# VS_Module.net
KiCad netlist of a schematic drawn in EasyEDA Pro
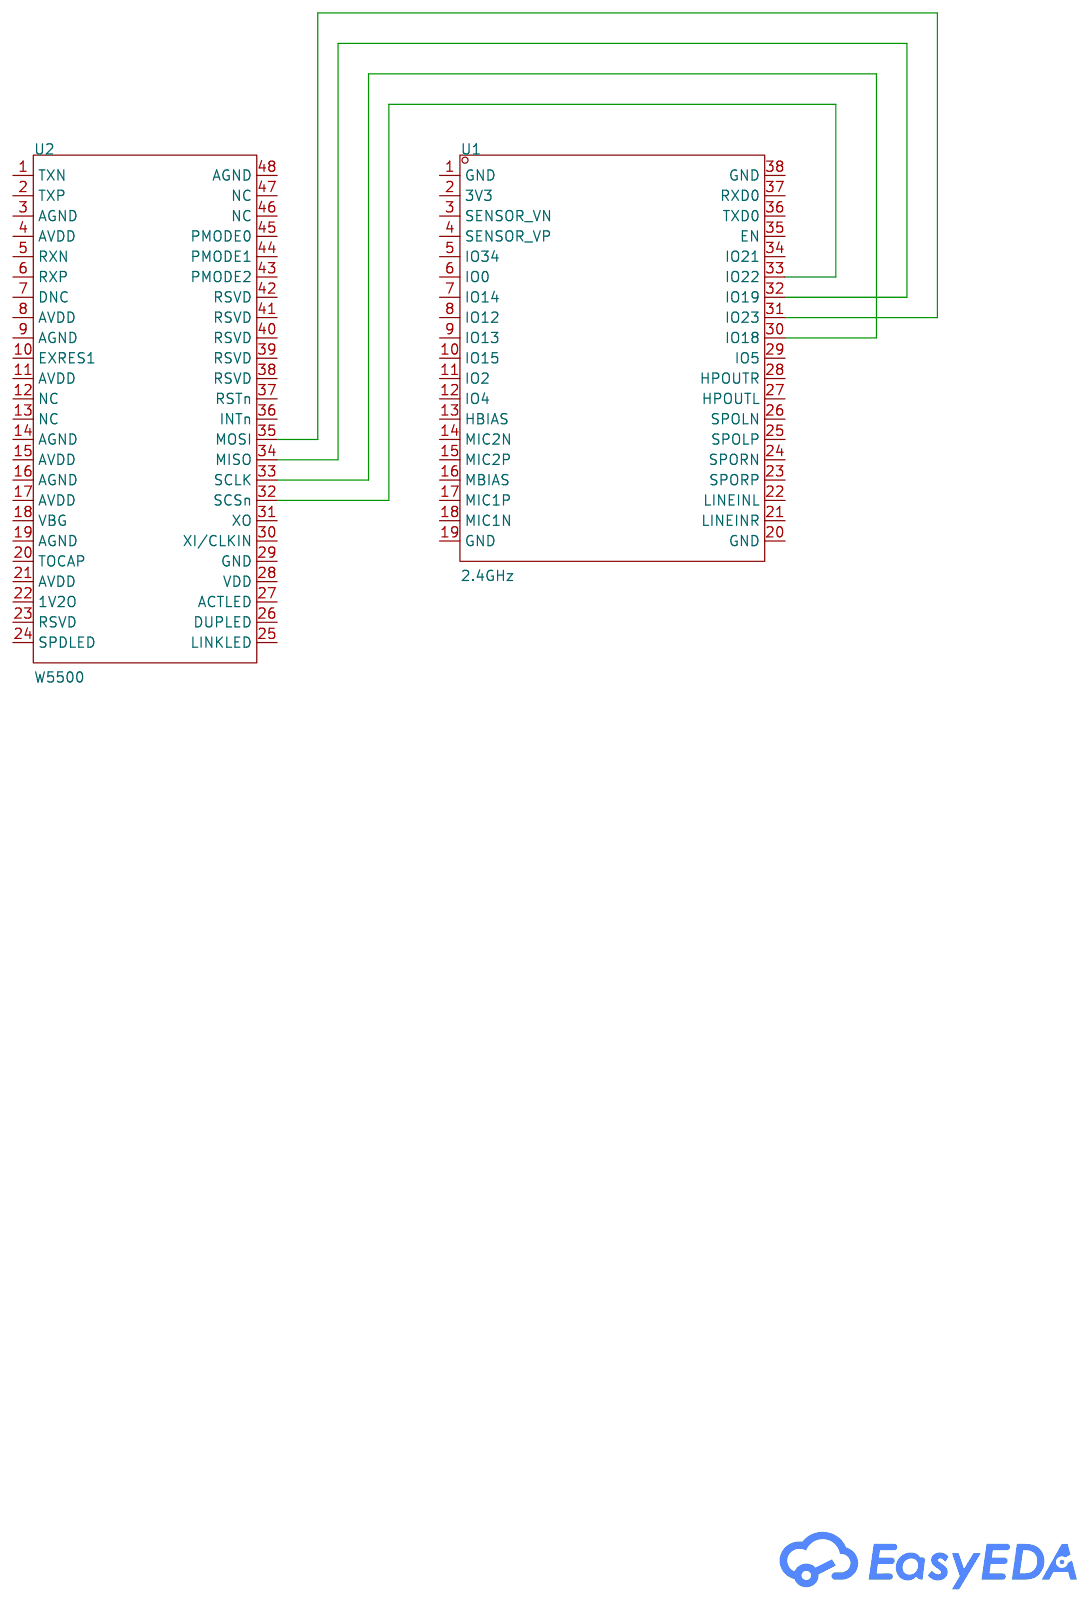
[diagram p0: schematic sheet]

(export (version "E")
  (design (tool "Eeschema 10.0.6"))
  (components
    (comp (ref "U1")
      (value "2.4GHz")
      (footprint "easyedapro:WIRELM-SMD_ESP32-A1S")
      (fields (field (name "Manufacturer Part") "ESP32-A1S") (field (name "Manufacturer") "Ai-Thinker(安信可)"))
      (libsource (lib "easyedapro") (part "ESP32-A1S"))
    )
    (comp (ref "U2")
      (value "W5500")
      (footprint "easyedapro:LQFP-48_L7.0-W7.0-P0.50-LS9.0-BL")
      (fields (field (name "Manufacturer") "WIZNET"))
      (libsource (lib "easyedapro") (part "W5500"))
    )
  )
  (nets
    (net (code "1") (name "Net-(U1-IO18)") (class "Default")
      (node (ref "U1") (pin "30") (pinfunction "IO18_30") (pintype "input"))
      (node (ref "U2") (pin "33") (pinfunction "SCLK_33") (pintype "unspecified"))
    )
    (net (code "2") (name "Net-(U1-IO19)") (class "Default")
      (node (ref "U1") (pin "32") (pinfunction "IO19_32") (pintype "input"))
      (node (ref "U2") (pin "34") (pinfunction "MISO_34") (pintype "unspecified"))
    )
    (net (code "3") (name "Net-(U1-IO22)") (class "Default")
      (node (ref "U1") (pin "33") (pinfunction "IO22_33") (pintype "input"))
      (node (ref "U2") (pin "32") (pinfunction "SCSn_32") (pintype "unspecified"))
    )
    (net (code "4") (name "Net-(U1-IO23)") (class "Default")
      (node (ref "U1") (pin "31") (pinfunction "IO23_31") (pintype "input"))
      (node (ref "U2") (pin "35") (pinfunction "MOSI_35") (pintype "unspecified"))
    )
    (net (code "5") (name "unconnected-(U1-3V3-Pad2)") (class "Default")
      (node (ref "U1") (pin "2") (pinfunction "3V3_2") (pintype "input"))
    )
    (net (code "6") (name "unconnected-(U1-EN-Pad35)") (class "Default")
      (node (ref "U1") (pin "35") (pinfunction "EN_35") (pintype "input"))
    )
    (net (code "7") (name "unconnected-(U1-GND-Pad1)") (class "Default")
      (node (ref "U1") (pin "1") (pinfunction "GND_1") (pintype "input"))
    )
    (net (code "8") (name "unconnected-(U1-GND-Pad19)") (class "Default")
      (node (ref "U1") (pin "19") (pinfunction "GND_19") (pintype "input"))
    )
    (net (code "9") (name "unconnected-(U1-GND-Pad20)") (class "Default")
      (node (ref "U1") (pin "20") (pinfunction "GND_20") (pintype "input"))
    )
    (net (code "10") (name "unconnected-(U1-GND-Pad38)") (class "Default")
      (node (ref "U1") (pin "38") (pinfunction "GND_38") (pintype "input"))
    )
    (net (code "11") (name "unconnected-(U1-HBIAS-Pad13)") (class "Default")
      (node (ref "U1") (pin "13") (pinfunction "HBIAS_13") (pintype "input"))
    )
    (net (code "12") (name "unconnected-(U1-HPOUTL-Pad27)") (class "Default")
      (node (ref "U1") (pin "27") (pinfunction "HPOUTL_27") (pintype "input"))
    )
    (net (code "13") (name "unconnected-(U1-HPOUTR-Pad28)") (class "Default")
      (node (ref "U1") (pin "28") (pinfunction "HPOUTR_28") (pintype "input"))
    )
    (net (code "14") (name "unconnected-(U1-IO0-Pad6)") (class "Default")
      (node (ref "U1") (pin "6") (pinfunction "IO0_6") (pintype "input"))
    )
    (net (code "15") (name "unconnected-(U1-IO2-Pad11)") (class "Default")
      (node (ref "U1") (pin "11") (pinfunction "IO2_11") (pintype "input"))
    )
    (net (code "16") (name "unconnected-(U1-IO4-Pad12)") (class "Default")
      (node (ref "U1") (pin "12") (pinfunction "IO4_12") (pintype "input"))
    )
    (net (code "17") (name "unconnected-(U1-IO5-Pad29)") (class "Default")
      (node (ref "U1") (pin "29") (pinfunction "IO5_29") (pintype "input"))
    )
    (net (code "18") (name "unconnected-(U1-IO12-Pad8)") (class "Default")
      (node (ref "U1") (pin "8") (pinfunction "IO12_8") (pintype "input"))
    )
    (net (code "19") (name "unconnected-(U1-IO13-Pad9)") (class "Default")
      (node (ref "U1") (pin "9") (pinfunction "IO13_9") (pintype "input"))
    )
    (net (code "20") (name "unconnected-(U1-IO14-Pad7)") (class "Default")
      (node (ref "U1") (pin "7") (pinfunction "IO14_7") (pintype "input"))
    )
    (net (code "21") (name "unconnected-(U1-IO15-Pad10)") (class "Default")
      (node (ref "U1") (pin "10") (pinfunction "IO15_10") (pintype "input"))
    )
    (net (code "22") (name "unconnected-(U1-IO21-Pad34)") (class "Default")
      (node (ref "U1") (pin "34") (pinfunction "IO21_34") (pintype "input"))
    )
    (net (code "23") (name "unconnected-(U1-IO34-Pad5)") (class "Default")
      (node (ref "U1") (pin "5") (pinfunction "IO34_5") (pintype "input"))
    )
    (net (code "24") (name "unconnected-(U1-LINEINL-Pad22)") (class "Default")
      (node (ref "U1") (pin "22") (pinfunction "LINEINL_22") (pintype "input"))
    )
    (net (code "25") (name "unconnected-(U1-LINEINR-Pad21)") (class "Default")
      (node (ref "U1") (pin "21") (pinfunction "LINEINR_21") (pintype "input"))
    )
    (net (code "26") (name "unconnected-(U1-MBIAS-Pad16)") (class "Default")
      (node (ref "U1") (pin "16") (pinfunction "MBIAS_16") (pintype "input"))
    )
    (net (code "27") (name "unconnected-(U1-MIC1N-Pad18)") (class "Default")
      (node (ref "U1") (pin "18") (pinfunction "MIC1N_18") (pintype "input"))
    )
    (net (code "28") (name "unconnected-(U1-MIC1P-Pad17)") (class "Default")
      (node (ref "U1") (pin "17") (pinfunction "MIC1P_17") (pintype "input"))
    )
    (net (code "29") (name "unconnected-(U1-MIC2N-Pad14)") (class "Default")
      (node (ref "U1") (pin "14") (pinfunction "MIC2N_14") (pintype "input"))
    )
    (net (code "30") (name "unconnected-(U1-MIC2P-Pad15)") (class "Default")
      (node (ref "U1") (pin "15") (pinfunction "MIC2P_15") (pintype "input"))
    )
    (net (code "31") (name "unconnected-(U1-RXD0-Pad37)") (class "Default")
      (node (ref "U1") (pin "37") (pinfunction "RXD0_37") (pintype "input"))
    )
    (net (code "32") (name "unconnected-(U1-SENSOR_VN-Pad3)") (class "Default")
      (node (ref "U1") (pin "3") (pinfunction "SENSOR_VN_3") (pintype "input"))
    )
    (net (code "33") (name "unconnected-(U1-SENSOR_VP-Pad4)") (class "Default")
      (node (ref "U1") (pin "4") (pinfunction "SENSOR_VP_4") (pintype "input"))
    )
    (net (code "34") (name "unconnected-(U1-SPOLN-Pad26)") (class "Default")
      (node (ref "U1") (pin "26") (pinfunction "SPOLN_26") (pintype "input"))
    )
    (net (code "35") (name "unconnected-(U1-SPOLP-Pad25)") (class "Default")
      (node (ref "U1") (pin "25") (pinfunction "SPOLP_25") (pintype "input"))
    )
    (net (code "36") (name "unconnected-(U1-SPORN-Pad24)") (class "Default")
      (node (ref "U1") (pin "24") (pinfunction "SPORN_24") (pintype "input"))
    )
    (net (code "37") (name "unconnected-(U1-SPORP-Pad23)") (class "Default")
      (node (ref "U1") (pin "23") (pinfunction "SPORP_23") (pintype "input"))
    )
    (net (code "38") (name "unconnected-(U1-TXD0-Pad36)") (class "Default")
      (node (ref "U1") (pin "36") (pinfunction "TXD0_36") (pintype "input"))
    )
    (net (code "39") (name "unconnected-(U2-1V2O-Pad22)") (class "Default")
      (node (ref "U2") (pin "22") (pinfunction "1V2O_22") (pintype "unspecified"))
    )
    (net (code "40") (name "unconnected-(U2-ACTLED-Pad27)") (class "Default")
      (node (ref "U2") (pin "27") (pinfunction "ACTLED_27") (pintype "unspecified"))
    )
    (net (code "41") (name "unconnected-(U2-AGND-Pad3)") (class "Default")
      (node (ref "U2") (pin "3") (pinfunction "AGND_3") (pintype "unspecified"))
    )
    (net (code "42") (name "unconnected-(U2-AGND-Pad9)") (class "Default")
      (node (ref "U2") (pin "9") (pinfunction "AGND_9") (pintype "unspecified"))
    )
    (net (code "43") (name "unconnected-(U2-AGND-Pad14)") (class "Default")
      (node (ref "U2") (pin "14") (pinfunction "AGND_14") (pintype "unspecified"))
    )
    (net (code "44") (name "unconnected-(U2-AGND-Pad16)") (class "Default")
      (node (ref "U2") (pin "16") (pinfunction "AGND_16") (pintype "unspecified"))
    )
    (net (code "45") (name "unconnected-(U2-AGND-Pad19)") (class "Default")
      (node (ref "U2") (pin "19") (pinfunction "AGND_19") (pintype "unspecified"))
    )
    (net (code "46") (name "unconnected-(U2-AGND-Pad48)") (class "Default")
      (node (ref "U2") (pin "48") (pinfunction "AGND_48") (pintype "unspecified"))
    )
    (net (code "47") (name "unconnected-(U2-AVDD-Pad4)") (class "Default")
      (node (ref "U2") (pin "4") (pinfunction "AVDD_4") (pintype "unspecified"))
    )
    (net (code "48") (name "unconnected-(U2-AVDD-Pad8)") (class "Default")
      (node (ref "U2") (pin "8") (pinfunction "AVDD_8") (pintype "unspecified"))
    )
    (net (code "49") (name "unconnected-(U2-AVDD-Pad11)") (class "Default")
      (node (ref "U2") (pin "11") (pinfunction "AVDD_11") (pintype "unspecified"))
    )
    (net (code "50") (name "unconnected-(U2-AVDD-Pad15)") (class "Default")
      (node (ref "U2") (pin "15") (pinfunction "AVDD_15") (pintype "unspecified"))
    )
    (net (code "51") (name "unconnected-(U2-AVDD-Pad17)") (class "Default")
      (node (ref "U2") (pin "17") (pinfunction "AVDD_17") (pintype "unspecified"))
    )
    (net (code "52") (name "unconnected-(U2-AVDD-Pad21)") (class "Default")
      (node (ref "U2") (pin "21") (pinfunction "AVDD_21") (pintype "unspecified"))
    )
    (net (code "53") (name "unconnected-(U2-DNC-Pad7)") (class "Default")
      (node (ref "U2") (pin "7") (pinfunction "DNC_7") (pintype "unspecified"))
    )
    (net (code "54") (name "unconnected-(U2-DUPLED-Pad26)") (class "Default")
      (node (ref "U2") (pin "26") (pinfunction "DUPLED_26") (pintype "unspecified"))
    )
    (net (code "55") (name "unconnected-(U2-EXRES1-Pad10)") (class "Default")
      (node (ref "U2") (pin "10") (pinfunction "EXRES1_10") (pintype "unspecified"))
    )
    (net (code "56") (name "unconnected-(U2-GND-Pad29)") (class "Default")
      (node (ref "U2") (pin "29") (pinfunction "GND_29") (pintype "unspecified"))
    )
    (net (code "57") (name "unconnected-(U2-INTn-Pad36)") (class "Default")
      (node (ref "U2") (pin "36") (pinfunction "INTn_36") (pintype "unspecified"))
    )
    (net (code "58") (name "unconnected-(U2-LINKLED-Pad25)") (class "Default")
      (node (ref "U2") (pin "25") (pinfunction "LINKLED_25") (pintype "unspecified"))
    )
    (net (code "59") (name "unconnected-(U2-NC-Pad12)") (class "Default")
      (node (ref "U2") (pin "12") (pinfunction "NC_12") (pintype "unspecified"))
    )
    (net (code "60") (name "unconnected-(U2-NC-Pad13)") (class "Default")
      (node (ref "U2") (pin "13") (pinfunction "NC_13") (pintype "unspecified"))
    )
    (net (code "61") (name "unconnected-(U2-NC-Pad46)") (class "Default")
      (node (ref "U2") (pin "46") (pinfunction "NC_46") (pintype "unspecified"))
    )
    (net (code "62") (name "unconnected-(U2-NC-Pad47)") (class "Default")
      (node (ref "U2") (pin "47") (pinfunction "NC_47") (pintype "unspecified"))
    )
    (net (code "63") (name "unconnected-(U2-PMODE0-Pad45)") (class "Default")
      (node (ref "U2") (pin "45") (pinfunction "PMODE0_45") (pintype "unspecified"))
    )
    (net (code "64") (name "unconnected-(U2-PMODE1-Pad44)") (class "Default")
      (node (ref "U2") (pin "44") (pinfunction "PMODE1_44") (pintype "unspecified"))
    )
    (net (code "65") (name "unconnected-(U2-PMODE2-Pad43)") (class "Default")
      (node (ref "U2") (pin "43") (pinfunction "PMODE2_43") (pintype "unspecified"))
    )
    (net (code "66") (name "unconnected-(U2-RSTn-Pad37)") (class "Default")
      (node (ref "U2") (pin "37") (pinfunction "RSTn_37") (pintype "unspecified"))
    )
    (net (code "67") (name "unconnected-(U2-RSVD-Pad23)") (class "Default")
      (node (ref "U2") (pin "23") (pinfunction "RSVD_23") (pintype "unspecified"))
    )
    (net (code "68") (name "unconnected-(U2-RSVD-Pad38)") (class "Default")
      (node (ref "U2") (pin "38") (pinfunction "RSVD_38") (pintype "unspecified"))
    )
    (net (code "69") (name "unconnected-(U2-RSVD-Pad39)") (class "Default")
      (node (ref "U2") (pin "39") (pinfunction "RSVD_39") (pintype "unspecified"))
    )
    (net (code "70") (name "unconnected-(U2-RSVD-Pad40)") (class "Default")
      (node (ref "U2") (pin "40") (pinfunction "RSVD_40") (pintype "unspecified"))
    )
    (net (code "71") (name "unconnected-(U2-RSVD-Pad41)") (class "Default")
      (node (ref "U2") (pin "41") (pinfunction "RSVD_41") (pintype "unspecified"))
    )
    (net (code "72") (name "unconnected-(U2-RSVD-Pad42)") (class "Default")
      (node (ref "U2") (pin "42") (pinfunction "RSVD_42") (pintype "unspecified"))
    )
    (net (code "73") (name "unconnected-(U2-RXN-Pad5)") (class "Default")
      (node (ref "U2") (pin "5") (pinfunction "RXN_5") (pintype "unspecified"))
    )
    (net (code "74") (name "unconnected-(U2-RXP-Pad6)") (class "Default")
      (node (ref "U2") (pin "6") (pinfunction "RXP_6") (pintype "unspecified"))
    )
    (net (code "75") (name "unconnected-(U2-SPDLED-Pad24)") (class "Default")
      (node (ref "U2") (pin "24") (pinfunction "SPDLED_24") (pintype "unspecified"))
    )
    (net (code "76") (name "unconnected-(U2-TOCAP-Pad20)") (class "Default")
      (node (ref "U2") (pin "20") (pinfunction "TOCAP_20") (pintype "unspecified"))
    )
    (net (code "77") (name "unconnected-(U2-TXN-Pad1)") (class "Default")
      (node (ref "U2") (pin "1") (pinfunction "TXN_1") (pintype "unspecified"))
    )
    (net (code "78") (name "unconnected-(U2-TXP-Pad2)") (class "Default")
      (node (ref "U2") (pin "2") (pinfunction "TXP_2") (pintype "unspecified"))
    )
    (net (code "79") (name "unconnected-(U2-VBG-Pad18)") (class "Default")
      (node (ref "U2") (pin "18") (pinfunction "VBG_18") (pintype "unspecified"))
    )
    (net (code "80") (name "unconnected-(U2-VDD-Pad28)") (class "Default")
      (node (ref "U2") (pin "28") (pinfunction "VDD_28") (pintype "unspecified"))
    )
    (net (code "81") (name "unconnected-(U2-XI{slash}CLKIN-Pad30)") (class "Default")
      (node (ref "U2") (pin "30") (pinfunction "XI/CLKIN_30") (pintype "unspecified"))
    )
    (net (code "82") (name "unconnected-(U2-XO-Pad31)") (class "Default")
      (node (ref "U2") (pin "31") (pinfunction "XO_31") (pintype "unspecified"))
    )
  )
)
